# Power_Input_and_Regulators.net
KiCad netlist of a schematic drawn in Altium Designer
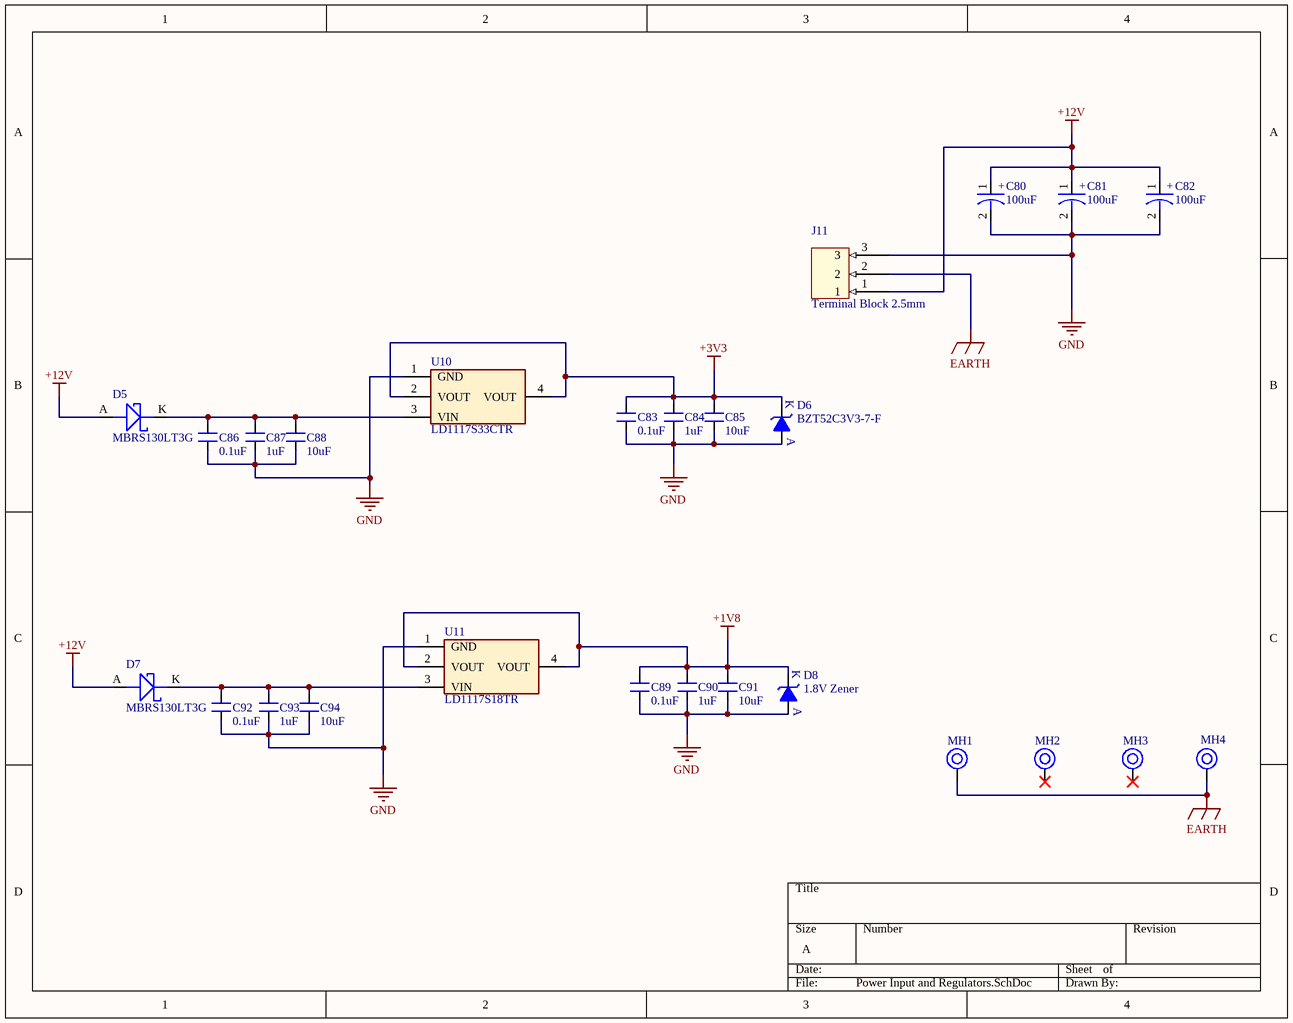
[diagram p0: Power Input and Regulators.SchDoc]

(export (version "E")
  (design (tool "Eeschema 10.0.6"))
  (components
    (comp (ref "C80")
      (value "100uF")
      (footprint "ACAP_P305_D393_H393_RAD")
      (description "100µF 50V Aluminum Polymer Capacitor Radial, Can - SMD 28mOhm 4000 Hrs @ 125°C")
      (fields
        (field (name "MANUFACTURER") "Nichicon")
        (field (name "MANUFACTURER PART NUMBER") "GYA1H101MCQ1GS")
      )
      (libsource (lib "ESTEEMPCBLIB") (part "CAP-P_100uF-50V-20%-RAD"))
    )
    (comp (ref "C81")
      (value "100uF")
      (footprint "ACAP_P305_D393_H393_RAD")
      (description "100µF 50V Aluminum Polymer Capacitor Radial, Can - SMD 28mOhm 4000 Hrs @ 125°C")
      (fields
        (field (name "MANUFACTURER") "Nichicon")
        (field (name "MANUFACTURER PART NUMBER") "GYA1H101MCQ1GS")
      )
      (libsource (lib "ESTEEMPCBLIB") (part "CAP-P_100uF-50V-20%-RAD"))
    )
    (comp (ref "C82")
      (value "100uF")
      (footprint "ACAP_P305_D393_H393_RAD")
      (description "100µF 50V Aluminum Polymer Capacitor Radial, Can - SMD 28mOhm 4000 Hrs @ 125°C")
      (fields
        (field (name "MANUFACTURER") "Nichicon")
        (field (name "MANUFACTURER PART NUMBER") "GYA1H101MCQ1GS")
      )
      (libsource (lib "ESTEEMPCBLIB") (part "CAP-P_100uF-50V-20%-RAD"))
    )
    (comp (ref "C83")
      (value "0.1uF")
      (footprint "CAP_0805")
      (description "0.1µF ±10% 50V Ceramic Capacitor X7R 0805 (2012 Metric)")
      (fields
        (field (name "MANUFACTURER") "Samsung")
        (field (name "MANUFACTURER PART NUMBER") "CL21B104KBCNNNC")
      )
      (libsource (lib "ESTEEMPCBLIB") (part "CAP_0.1uF-50V-10%-0805"))
    )
    (comp (ref "C84")
      (value "1uF")
      (footprint "CAP_0805")
      (description "1µF ±5% 50V Ceramic Capacitor X7R 0805 (2012 Metric)")
      (fields
        (field (name "MANUFACTURER") "Samsung")
        (field (name "MANUFACTURER PART NUMBER") "CC0805JKX7R9BB105")
      )
      (libsource (lib "ESTEEMPCBLIB") (part "CAP_1uF-50V-5%-0805"))
    )
    (comp (ref "C85")
      (value "10uF")
      (footprint "CAP_1206")
      (description "10µF ±10% 50V Ceramic Capacitor X7R 1206 (3216 Metric)")
      (fields
        (field (name "MANUFACTURER") "KEMET")
        (field (name "MANUFACTURER PART NUMBER") "CL31B106KBHNNNE")
      )
      (libsource (lib "ESTEEMPCBLIB") (part "CAP_10uF-50V-10%-1206"))
    )
    (comp (ref "C86")
      (value "0.1uF")
      (footprint "CAP_0805")
      (description "0.1µF ±10% 50V Ceramic Capacitor X7R 0805 (2012 Metric)")
      (fields
        (field (name "MANUFACTURER") "Samsung")
        (field (name "MANUFACTURER PART NUMBER") "CL21B104KBCNNNC")
      )
      (libsource (lib "ESTEEMPCBLIB") (part "CAP_0.1uF-50V-10%-0805"))
    )
    (comp (ref "C87")
      (value "1uF")
      (footprint "CAP_0805")
      (description "1µF ±5% 50V Ceramic Capacitor X7R 0805 (2012 Metric)")
      (fields
        (field (name "MANUFACTURER") "Samsung")
        (field (name "MANUFACTURER PART NUMBER") "CC0805JKX7R9BB105")
      )
      (libsource (lib "ESTEEMPCBLIB") (part "CAP_1uF-50V-5%-0805"))
    )
    (comp (ref "C88")
      (value "10uF")
      (footprint "CAP_1206")
      (description "10µF ±10% 50V Ceramic Capacitor X7R 1206 (3216 Metric)")
      (fields
        (field (name "MANUFACTURER") "KEMET")
        (field (name "MANUFACTURER PART NUMBER") "CL31B106KBHNNNE")
      )
      (libsource (lib "ESTEEMPCBLIB") (part "CAP_10uF-50V-10%-1206"))
    )
    (comp (ref "C89")
      (value "0.1uF")
      (footprint "CAP_0805")
      (description "0.1µF ±10% 50V Ceramic Capacitor X7R 0805 (2012 Metric)")
      (fields
        (field (name "MANUFACTURER") "Samsung")
        (field (name "MANUFACTURER PART NUMBER") "CL21B104KBCNNNC")
      )
      (libsource (lib "ESTEEMPCBLIB") (part "CAP_0.1uF-50V-10%-0805"))
    )
    (comp (ref "C90")
      (value "1uF")
      (footprint "CAP_0805")
      (description "1µF ±5% 50V Ceramic Capacitor X7R 0805 (2012 Metric)")
      (fields
        (field (name "MANUFACTURER") "Samsung")
        (field (name "MANUFACTURER PART NUMBER") "CC0805JKX7R9BB105")
      )
      (libsource (lib "ESTEEMPCBLIB") (part "CAP_1uF-50V-5%-0805"))
    )
    (comp (ref "C91")
      (value "10uF")
      (footprint "CAP_1206")
      (description "10µF ±10% 50V Ceramic Capacitor X7R 1206 (3216 Metric)")
      (fields
        (field (name "MANUFACTURER") "KEMET")
        (field (name "MANUFACTURER PART NUMBER") "CL31B106KBHNNNE")
      )
      (libsource (lib "ESTEEMPCBLIB") (part "CAP_10uF-50V-10%-1206"))
    )
    (comp (ref "C92")
      (value "0.1uF")
      (footprint "CAP_0805")
      (description "0.1µF ±10% 50V Ceramic Capacitor X7R 0805 (2012 Metric)")
      (fields
        (field (name "MANUFACTURER") "Samsung")
        (field (name "MANUFACTURER PART NUMBER") "CL21B104KBCNNNC")
      )
      (libsource (lib "ESTEEMPCBLIB") (part "CAP_0.1uF-50V-10%-0805"))
    )
    (comp (ref "C93")
      (value "1uF")
      (footprint "CAP_0805")
      (description "1µF ±5% 50V Ceramic Capacitor X7R 0805 (2012 Metric)")
      (fields
        (field (name "MANUFACTURER") "Samsung")
        (field (name "MANUFACTURER PART NUMBER") "CC0805JKX7R9BB105")
      )
      (libsource (lib "ESTEEMPCBLIB") (part "CAP_1uF-50V-5%-0805"))
    )
    (comp (ref "C94")
      (value "10uF")
      (footprint "CAP_1206")
      (description "10µF ±10% 50V Ceramic Capacitor X7R 1206 (3216 Metric)")
      (fields
        (field (name "MANUFACTURER") "KEMET")
        (field (name "MANUFACTURER PART NUMBER") "CL31B106KBHNNNE")
      )
      (libsource (lib "ESTEEMPCBLIB") (part "CAP_10uF-50V-10%-1206"))
    )
    (comp (ref "D5")
      (value "MBRS130LT3G")
      (footprint "DIO_SMB_DO-214AA")
      (description "Diode Schottky 30V 2A Surface Mount SMB")
      (fields (field (name "MANUFACTURER") "ON Semiconductor"))
      (libsource (lib "ESTEEMPCBLIB") (part "DIO-S_445mV-30V-2A-SMB"))
    )
    (comp (ref "D6")
      (value "BZT52C3V3-7-F")
      (footprint "DIO_SOD-123")
      (description "Zener Diode 3.3V 500mW ±6% Surface Mount SOD-123")
      (fields (field (name "MANUFACTURER") "Diodes Incorporated"))
      (libsource (lib "ESTEEMPCBLIB") (part "DIO-Z_3.3V-500mW-SOD123"))
    )
    (comp (ref "D7")
      (value "MBRS130LT3G")
      (footprint "DIO_SMB_DO-214AA")
      (description "Diode Schottky 30V 2A Surface Mount SMB")
      (fields (field (name "MANUFACTURER") "ON Semiconductor"))
      (libsource (lib "ESTEEMPCBLIB") (part "DIO-S_445mV-30V-2A-SMB"))
    )
    (comp (ref "D8")
      (value "1.8V Zener")
      (footprint "DIO_DO-213AB_SMD")
      (description "Zener Diode 1.8V 500mW ±5% Surface Mount DO-213AA")
      (libsource (lib "ESTEEMPCBLIB") (part "DIO-Z_1.8V-500mW-DO213AA"))
    )
    (comp (ref "J11")
      (value "Terminal Block 2.5mm")
      (footprint "CON3_100_TB_TH_ST")
      (description "3 Pins, 1 Row 2.54mm Pitch, straight Connector, male")
      (fields
        (field (name "MANUFACTURER PART NUMBER") "1725669")
        (field (name "MANUFACTURER") "Phoenix Contact")
      )
      (libsource (lib "ESTEEMPCBLIB") (part "CON-TB_3X1-100-ST-TH"))
    )
    (comp (ref "MH1")
      (value "Mounting Hole")
      (footprint "MOUNTING")
      (fields (field (name "MANUFACTURER PART NUMBER") "NA"))
      (libsource (lib "ESTEEMPCBLIB") (part "MH_3.5H_6D"))
    )
    (comp (ref "MH2")
      (value "Mounting Hole")
      (footprint "MOUNTING")
      (fields (field (name "MANUFACTURER PART NUMBER") "NA"))
      (libsource (lib "ESTEEMPCBLIB") (part "MH_3.5H_6D"))
    )
    (comp (ref "MH3")
      (value "Mounting Hole")
      (footprint "MOUNTING")
      (fields (field (name "MANUFACTURER PART NUMBER") "NA"))
      (libsource (lib "ESTEEMPCBLIB") (part "MH_3.5H_6D"))
    )
    (comp (ref "MH4")
      (value "Mounting Hole")
      (footprint "MOUNTING")
      (fields (field (name "MANUFACTURER PART NUMBER") "NA"))
      (libsource (lib "ESTEEMPCBLIB") (part "MH_3.5H_6D"))
    )
    (comp (ref "U10")
      (value "LD1117S33CTR")
      (footprint "SOT223_3")
      (description "Linear Voltage Regulator IC 1 Output 800mA SOT-223")
      (fields (field (name "MANUFACTURER") "STMicroelectronics"))
      (libsource (lib "ESTEEMPCBLIB") (part "REG_15V-3.3V-0.9A-12W-SOT223"))
    )
    (comp (ref "U11")
      (value "LD1117S18TR")
      (footprint "SOT223_3")
      (description "LDO Voltage Regulators 1.8V 0.8A Positive")
      (fields (field (name "MANUFACTURER") "STMicroelectronics"))
      (libsource (lib "ESTEEMPCBLIB") (part "REG_15V-1.8V-0.8A-1.4W-SOT223"))
    )
  )
  (nets
    (net (code "1") (name "+1V8") (class "Default")
      (node (ref "C89") (pin "2") (pinfunction "2_2") (pintype "passive"))
      (node (ref "C90") (pin "2") (pinfunction "2_2") (pintype "passive"))
      (node (ref "C91") (pin "2") (pinfunction "2_2") (pintype "passive"))
      (node (ref "D8") (pin "K") (pinfunction "K_K") (pintype "passive"))
      (node (ref "U11") (pin "2") (pinfunction "VOUT_2") (pintype "passive"))
      (node (ref "U11") (pin "4") (pinfunction "VOUT_4") (pintype "passive"))
    )
    (net (code "2") (name "+3V3") (class "Default")
      (node (ref "C83") (pin "2") (pinfunction "2_2") (pintype "passive"))
      (node (ref "C84") (pin "2") (pinfunction "2_2") (pintype "passive"))
      (node (ref "C85") (pin "2") (pinfunction "2_2") (pintype "passive"))
      (node (ref "D6") (pin "K") (pinfunction "K_K") (pintype "passive"))
      (node (ref "U10") (pin "2") (pinfunction "VOUT_2") (pintype "passive"))
      (node (ref "U10") (pin "4") (pinfunction "VOUT_4") (pintype "passive"))
    )
    (net (code "3") (name "+12V") (class "Default")
      (node (ref "C80") (pin "1") (pinfunction "1_1") (pintype "passive"))
      (node (ref "C81") (pin "1") (pinfunction "1_1") (pintype "passive"))
      (node (ref "C82") (pin "1") (pinfunction "1_1") (pintype "passive"))
      (node (ref "D5") (pin "A") (pinfunction "A_A") (pintype "passive"))
      (node (ref "D7") (pin "A") (pinfunction "A_A") (pintype "passive"))
      (node (ref "J11") (pin "1") (pinfunction "1_1") (pintype "input"))
    )
    (net (code "4") (name "EARTH") (class "Default")
      (node (ref "J11") (pin "2") (pinfunction "2_2") (pintype "input"))
      (node (ref "MH1") (pin "1") (pinfunction "1_1") (pintype "passive"))
      (node (ref "MH4") (pin "1") (pinfunction "1_1") (pintype "passive"))
    )
    (net (code "5") (name "GND") (class "Default")
      (node (ref "C80") (pin "2") (pinfunction "2_2") (pintype "passive"))
      (node (ref "C81") (pin "2") (pinfunction "2_2") (pintype "passive"))
      (node (ref "C82") (pin "2") (pinfunction "2_2") (pintype "passive"))
      (node (ref "C83") (pin "1") (pinfunction "1_1") (pintype "passive"))
      (node (ref "C84") (pin "1") (pinfunction "1_1") (pintype "passive"))
      (node (ref "C85") (pin "1") (pinfunction "1_1") (pintype "passive"))
      (node (ref "C86") (pin "1") (pinfunction "1_1") (pintype "passive"))
      (node (ref "C87") (pin "1") (pinfunction "1_1") (pintype "passive"))
      (node (ref "C88") (pin "1") (pinfunction "1_1") (pintype "passive"))
      (node (ref "C89") (pin "1") (pinfunction "1_1") (pintype "passive"))
      (node (ref "C90") (pin "1") (pinfunction "1_1") (pintype "passive"))
      (node (ref "C91") (pin "1") (pinfunction "1_1") (pintype "passive"))
      (node (ref "C92") (pin "1") (pinfunction "1_1") (pintype "passive"))
      (node (ref "C93") (pin "1") (pinfunction "1_1") (pintype "passive"))
      (node (ref "C94") (pin "1") (pinfunction "1_1") (pintype "passive"))
      (node (ref "D6") (pin "A") (pinfunction "A_A") (pintype "passive"))
      (node (ref "D8") (pin "A") (pinfunction "A_A") (pintype "passive"))
      (node (ref "J11") (pin "3") (pinfunction "3_3") (pintype "input"))
      (node (ref "U10") (pin "1") (pinfunction "GND_1") (pintype "passive"))
      (node (ref "U11") (pin "1") (pinfunction "GND_1") (pintype "passive"))
    )
    (net (code "6") (name "Net-(U10-VIN)") (class "Default")
      (node (ref "C86") (pin "2") (pinfunction "2_2") (pintype "passive"))
      (node (ref "C87") (pin "2") (pinfunction "2_2") (pintype "passive"))
      (node (ref "C88") (pin "2") (pinfunction "2_2") (pintype "passive"))
      (node (ref "D5") (pin "K") (pinfunction "K_K") (pintype "passive"))
      (node (ref "U10") (pin "3") (pinfunction "VIN_3") (pintype "passive"))
    )
    (net (code "7") (name "Net-(U11-VIN)") (class "Default")
      (node (ref "C92") (pin "2") (pinfunction "2_2") (pintype "passive"))
      (node (ref "C93") (pin "2") (pinfunction "2_2") (pintype "passive"))
      (node (ref "C94") (pin "2") (pinfunction "2_2") (pintype "passive"))
      (node (ref "D7") (pin "K") (pinfunction "K_K") (pintype "passive"))
      (node (ref "U11") (pin "3") (pinfunction "VIN_3") (pintype "passive"))
    )
    (net (code "8") (name "unconnected-(MH2-Pad1)") (class "Default")
      (node (ref "MH2") (pin "1") (pinfunction "1_1") (pintype "passive+no_connect"))
    )
    (net (code "9") (name "unconnected-(MH3-Pad1)") (class "Default")
      (node (ref "MH3") (pin "1") (pinfunction "1_1") (pintype "passive+no_connect"))
    )
  )
)
